# LCDTFT_FPC30P_LVDS.net
KiCad netlist of a schematic drawn in Altium Designer
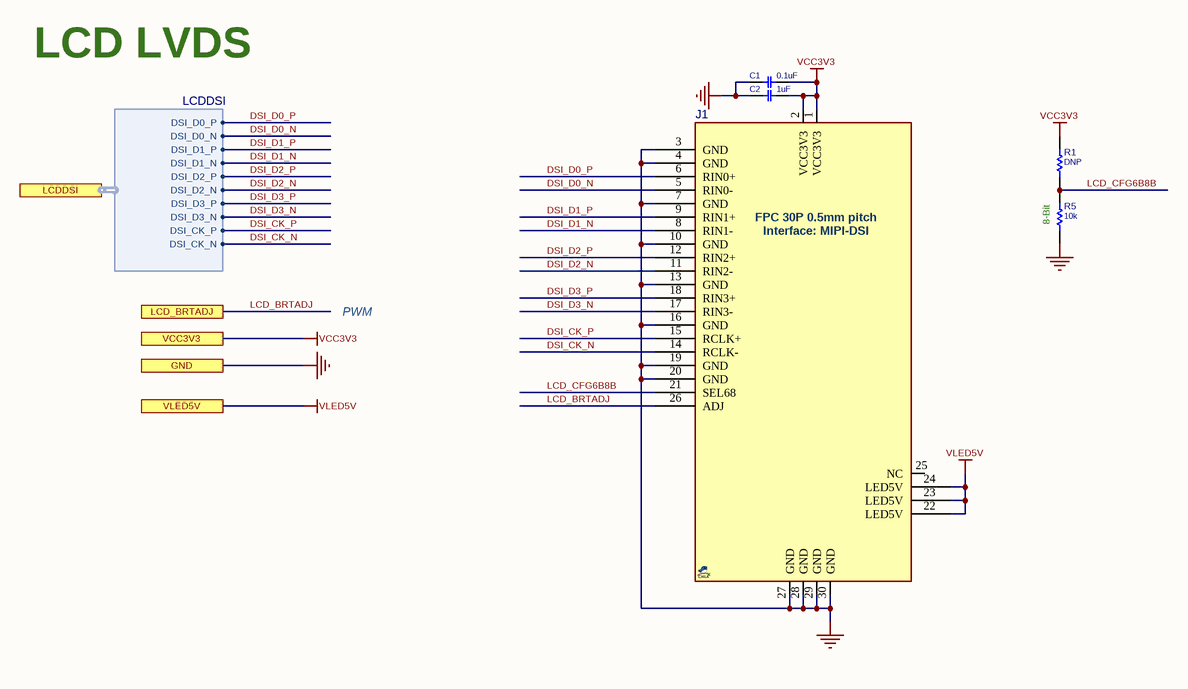
[diagram p0: LCDTFT_FPC30P_LVDS.SchDoc]

(export (version "E")
  (design (tool "Eeschema 10.0.6"))
  (components
    (comp (ref "C1")
      (value "0.1uF")
      (footprint "C0402")
      (description "CAP, MLCC")
      (fields (field (name "MANF_P#") "GRM155R71H104KE14D") (field (name "MANF") "Murata"))
      (libsource (lib "passive_smd") (part "CAP_SMD_MLCC"))
    )
    (comp (ref "C2")
      (value "1uF")
      (footprint "C0402")
      (description "CAP, MLCC")
      (fields (field (name "MANF_P#") "CL05A105KO5NNND") (field (name "MANF") "Samsung"))
      (libsource (lib "passive_smd") (part "CAP_SMD_MLCC"))
    )
    (comp (ref "J1")
      (value "FPC_30_0.5mm")
      (footprint "FPC50_30")
      (description "LCD TFT Color, FPC30P, LVDS")
      (libsource (lib "lcdtft") (part "LCDTFT_DSI_FPC30P"))
    )
    (comp (ref "R1")
      (value "DNP")
      (footprint "R0402")
      (description "RESISTOR, SMD")
      (libsource (lib "passive_res_smd") (part "RES_SMD"))
    )
    (comp (ref "R5")
      (value "10k")
      (footprint "R0402")
      (description "RESISTOR, SMD")
      (libsource (lib "passive_res_smd") (part "RES_SMD"))
    )
  )
  (nets
    (net (code "2") (name "/DSI_CK_N") (class "Default")
      (node (ref "J1") (pin "14") (pinfunction "RCLK-_14") (pintype "passive"))
    )
    (net (code "3") (name "/DSI_CK_P") (class "Default")
      (node (ref "J1") (pin "15") (pinfunction "RCLK+_15") (pintype "passive"))
    )
    (net (code "4") (name "/DSI_D0_N") (class "Default")
      (node (ref "J1") (pin "5") (pinfunction "RIN0-_5") (pintype "passive"))
    )
    (net (code "5") (name "/DSI_D0_P") (class "Default")
      (node (ref "J1") (pin "6") (pinfunction "RIN0+_6") (pintype "passive"))
    )
    (net (code "6") (name "/DSI_D1_N") (class "Default")
      (node (ref "J1") (pin "8") (pinfunction "RIN1-_8") (pintype "passive"))
    )
    (net (code "7") (name "/DSI_D1_P") (class "Default")
      (node (ref "J1") (pin "9") (pinfunction "RIN1+_9") (pintype "passive"))
    )
    (net (code "8") (name "/DSI_D2_N") (class "Default")
      (node (ref "J1") (pin "11") (pinfunction "RIN2-_11") (pintype "passive"))
    )
    (net (code "9") (name "/DSI_D2_P") (class "Default")
      (node (ref "J1") (pin "12") (pinfunction "RIN2+_12") (pintype "passive"))
    )
    (net (code "10") (name "/DSI_D3_N") (class "Default")
      (node (ref "J1") (pin "17") (pinfunction "RIN3-_17") (pintype "passive"))
    )
    (net (code "11") (name "/DSI_D3_P") (class "Default")
      (node (ref "J1") (pin "18") (pinfunction "RIN3+_18") (pintype "passive"))
    )
    (net (code "12") (name "/LCD_BRTADJ") (class "Default")
      (node (ref "J1") (pin "26") (pinfunction "ADJ_26") (pintype "passive"))
    )
    (net (code "13") (name "/LCD_CFG6B8B") (class "Default")
      (node (ref "J1") (pin "21") (pinfunction "SEL68_21") (pintype "passive"))
      (node (ref "R1") (pin "2") (pinfunction "2_2") (pintype "passive"))
      (node (ref "R5") (pin "1") (pinfunction "1_1") (pintype "passive"))
    )
    (net (code "15") (name "GND") (class "Default")
      (node (ref "C1") (pin "2") (pinfunction "2_2") (pintype "passive"))
      (node (ref "C2") (pin "2") (pinfunction "2_2") (pintype "passive"))
      (node (ref "J1") (pin "10") (pinfunction "GND_10") (pintype "passive"))
      (node (ref "J1") (pin "13") (pinfunction "GND_13") (pintype "passive"))
      (node (ref "J1") (pin "16") (pinfunction "GND_16") (pintype "passive"))
      (node (ref "J1") (pin "19") (pinfunction "GND_19") (pintype "passive"))
      (node (ref "J1") (pin "20") (pinfunction "GND_20") (pintype "passive"))
      (node (ref "J1") (pin "27") (pinfunction "GND_27") (pintype "passive"))
      (node (ref "J1") (pin "28") (pinfunction "GND_28") (pintype "passive"))
      (node (ref "J1") (pin "29") (pinfunction "GND_29") (pintype "passive"))
      (node (ref "J1") (pin "3") (pinfunction "GND_3") (pintype "passive"))
      (node (ref "J1") (pin "30") (pinfunction "GND_30") (pintype "passive"))
      (node (ref "J1") (pin "4") (pinfunction "GND_4") (pintype "passive"))
      (node (ref "J1") (pin "7") (pinfunction "GND_7") (pintype "passive"))
      (node (ref "R5") (pin "2") (pinfunction "2_2") (pintype "passive"))
    )
    (net (code "16") (name "VCC3V3") (class "Default")
      (node (ref "C1") (pin "1") (pinfunction "1_1") (pintype "passive"))
      (node (ref "C2") (pin "1") (pinfunction "1_1") (pintype "passive"))
      (node (ref "J1") (pin "1") (pinfunction "VCC3V3_1") (pintype "passive"))
      (node (ref "J1") (pin "2") (pinfunction "VCC3V3_2") (pintype "passive"))
      (node (ref "R1") (pin "1") (pinfunction "1_1") (pintype "passive"))
    )
    (net (code "17") (name "VLED5V") (class "Default")
      (node (ref "J1") (pin "22") (pinfunction "LED5V_22") (pintype "passive"))
      (node (ref "J1") (pin "23") (pinfunction "LED5V_23") (pintype "passive"))
      (node (ref "J1") (pin "24") (pinfunction "LED5V_24") (pintype "passive"))
    )
    (net (code "18") (name "unconnected-(J1-NC-Pad25)") (class "Default")
      (node (ref "J1") (pin "25") (pinfunction "NC_25") (pintype "passive"))
    )
  )
)
